# UNI_sensor.net
KiCad netlist of a schematic drawn in Altium Designer
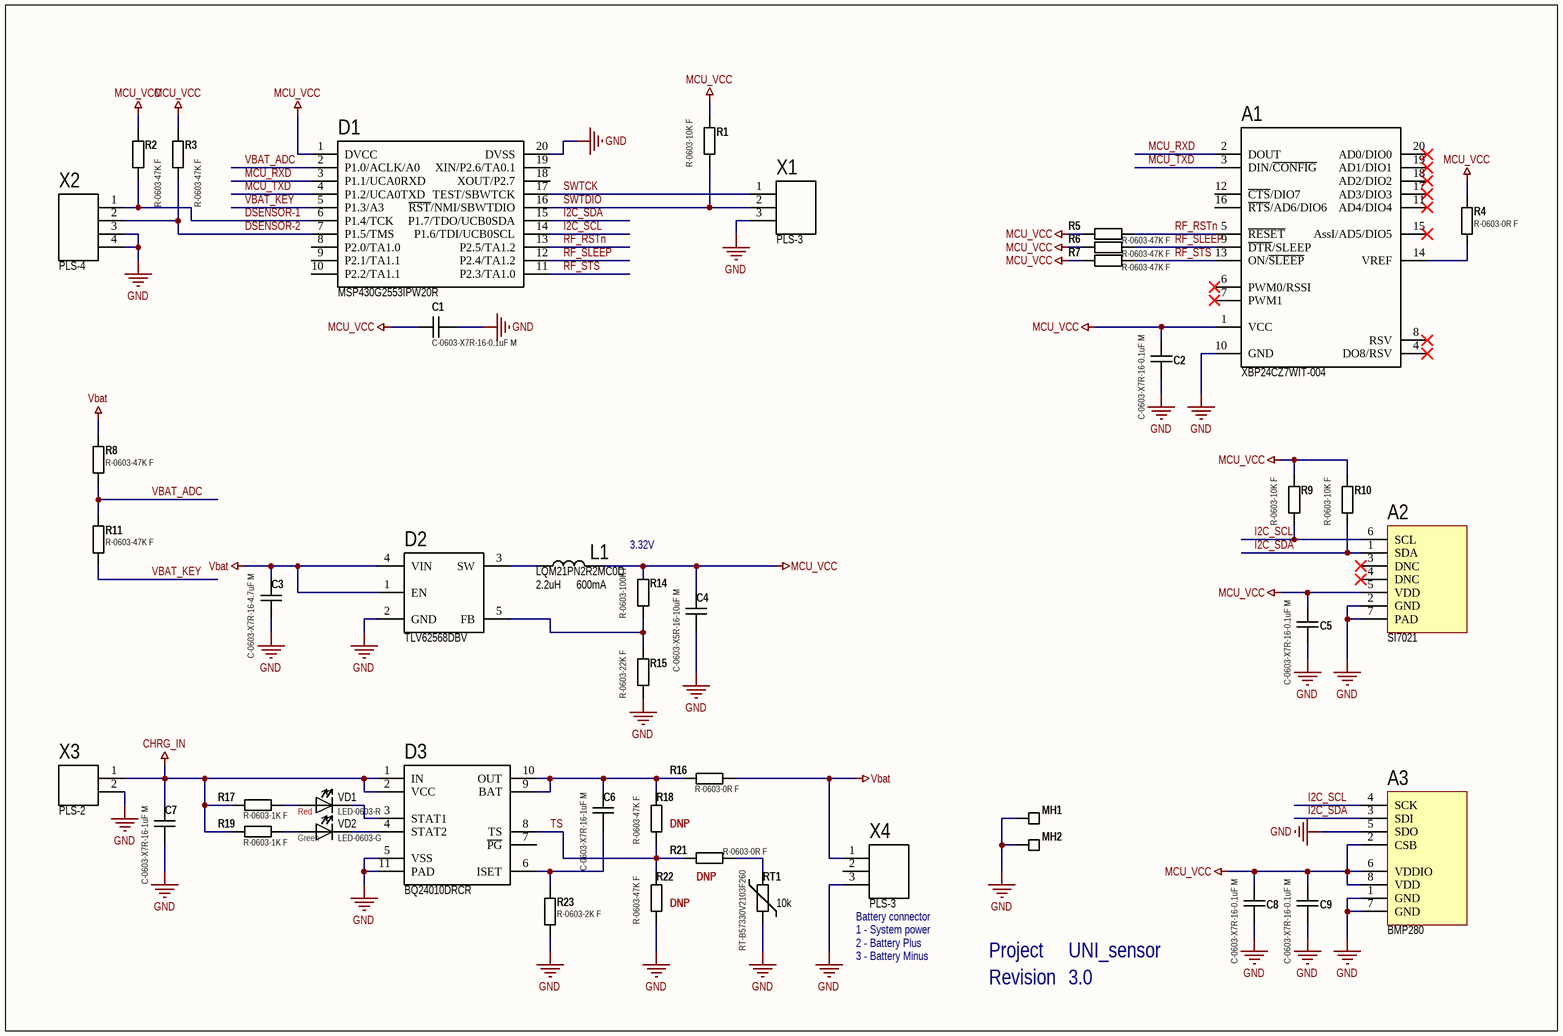
[diagram p0: UNI_sensor.SchDoc]

(export (version "E")
  (design (tool "Eeschema 10.0.6"))
  (components
    (comp (ref "A1")
      (value "XBP24CZ7WIT-004")
      (footprint "XBEE")
      (description "XBee Module")
      (fields (field (name "MANUFACTURER") "Digi"))
      (libsource (lib "Misc") (part "XBP24CZ7WIT"))
    )
    (comp (ref "A2")
      (value "SI7021")
      (footprint "SI7021")
      (description "I2C HUMIDITY AND TEMPERATURE SENSOR")
      (fields (field (name "MANUFACTURER") "Silicon Labs"))
      (libsource (lib "Misc") (part "SI7021"))
    )
    (comp (ref "A3")
      (value "BMP280")
      (footprint "BMP280")
      (description "Digital Pressure Sensor")
      (fields (field (name "MANUFACTURER") "Bosch Sensortec"))
      (libsource (lib "Misc") (part "BMP280"))
    )
    (comp (ref "C1")
      (value "C-0603-X7R-16-0.1uF M")
      (footprint "CAPC160X80X100L35N")
      (description "General capacitor")
      (fields (field (name "TOLERANCE") "20%") (field (name "MANUFACTURER") "Murata"))
      (libsource (lib "Passive") (part "C"))
    )
    (comp (ref "C2")
      (value "C-0603-X7R-16-0.1uF M")
      (footprint "CAPC160X80X100L35N")
      (description "General capacitor")
      (fields (field (name "TOLERANCE") "20%") (field (name "MANUFACTURER") "Murata"))
      (libsource (lib "Passive") (part "C"))
    )
    (comp (ref "C3")
      (value "C-0603-X7R-16-4.7uF M")
      (footprint "CAPC160X80X100L35N")
      (description "General capacitor")
      (fields (field (name "TOLERANCE") "20%") (field (name "MANUFACTURER") "Murata"))
      (libsource (lib "Passive") (part "C"))
    )
    (comp (ref "C4")
      (value "C-0603-X5R-16-10uF M")
      (footprint "CAPC160X80X100L35N")
      (description "General capacitor")
      (fields (field (name "TOLERANCE") "20%") (field (name "MANUFACTURER") "Murata"))
      (libsource (lib "Passive") (part "C"))
    )
    (comp (ref "C5")
      (value "C-0603-X7R-16-0.1uF M")
      (footprint "CAPC160X80X100L35N")
      (description "General capacitor")
      (fields (field (name "TOLERANCE") "20%") (field (name "MANUFACTURER") "Murata"))
      (libsource (lib "Passive") (part "C"))
    )
    (comp (ref "C6")
      (value "C-0603-X7R-16-1uF M")
      (footprint "CAPC160X80X100L35N")
      (description "General capacitor")
      (fields (field (name "TOLERANCE") "20%") (field (name "MANUFACTURER") "Murata"))
      (libsource (lib "Passive") (part "C"))
    )
    (comp (ref "C7")
      (value "C-0603-X7R-16-1uF M")
      (footprint "CAPC160X80X100L35N")
      (description "General capacitor")
      (fields (field (name "TOLERANCE") "20%") (field (name "MANUFACTURER") "Murata"))
      (libsource (lib "Passive") (part "C"))
    )
    (comp (ref "C8")
      (value "C-0603-X7R-16-0.1uF M")
      (footprint "CAPC160X80X100L35N")
      (description "General capacitor")
      (fields (field (name "TOLERANCE") "20%") (field (name "MANUFACTURER") "Murata"))
      (libsource (lib "Passive") (part "C"))
    )
    (comp (ref "C9")
      (value "C-0603-X7R-16-0.1uF M")
      (footprint "CAPC160X80X100L35N")
      (description "General capacitor")
      (fields (field (name "TOLERANCE") "20%") (field (name "MANUFACTURER") "Murata"))
      (libsource (lib "Passive") (part "C"))
    )
    (comp (ref "D1")
      (value "MSP430G2553IPW20R")
      (footprint "TSSOP-20")
      (description "16-bit microcontroller")
      (fields (field (name "MANUFACTURER") "Texas Instruments"))
      (libsource (lib "ICs") (part "MSP430G2553IPW20R"))
    )
    (comp (ref "D2")
      (value "TLV62568DBV")
      (footprint "SOT23-5")
      (description "1-A High Efficiency Synchronous Buck Converterin SOT Package")
      (fields (field (name "MANUFACTURER") "Texas Instruments"))
      (libsource (lib "ICs") (part "TLV62568DBV"))
    )
    (comp (ref "D3")
      (value "BQ24010DRCR")
      (footprint "QFN-11 (3x3)")
      (description "Single-Chip, Li-Ion Charge Management IC for Handheld Applications (bqTINY™)")
      (fields (field (name "MANUFACTURER") "Texas Instruments"))
      (libsource (lib "ICs") (part "BQ24010"))
    )
    (comp (ref "L1")
      (value "LQM21PN2R2MC0D")
      (footprint "L0805_BLM21")
      (description "General inductor")
      (fields
        (field (name "MANUFACTURER") "Murata")
        (field (name "ALTIUM_VALUE") "2.2uH")
        (field (name "TOLERANCE") "20%")
        (field (name "MAXCURRENT") "600mA")
      )
      (libsource (lib "Passive") (part "L"))
    )
    (comp (ref "MH1")
      (value "Testpoint")
      (footprint "REPER_2019:MHole_3.5_6mm")
      (description "Test point")
      (libsource (lib "Main_2019") (part "Test_point"))
    )
    (comp (ref "MH2")
      (value "Testpoint")
      (footprint "REPER_2019:MHole_3.5_6mm")
      (description "Test point")
      (libsource (lib "Main_2019") (part "Test_point"))
    )
    (comp (ref "R1")
      (value "R-0603-10K F")
      (footprint "RESC160X80X55L30N")
      (description "General resistor")
      (fields (field (name "MANUFACTURER") "Yageo") (field (name "TOLERANCE") "1%"))
      (libsource (lib "Passive") (part "R"))
    )
    (comp (ref "R2")
      (value "R-0603-47K F")
      (footprint "RESC160X80X55L30N")
      (description "General resistor")
      (fields (field (name "MANUFACTURER") "Yageo") (field (name "TOLERANCE") "1%"))
      (libsource (lib "Passive") (part "R"))
    )
    (comp (ref "R3")
      (value "R-0603-47K F")
      (footprint "RESC160X80X55L30N")
      (description "General resistor")
      (fields (field (name "MANUFACTURER") "Yageo") (field (name "TOLERANCE") "1%"))
      (libsource (lib "Passive") (part "R"))
    )
    (comp (ref "R4")
      (value "R-0603-0R F")
      (footprint "RESC160X80X55L30N")
      (description "General resistor")
      (fields (field (name "MANUFACTURER") "Yageo"))
      (libsource (lib "Passive") (part "R"))
    )
    (comp (ref "R5")
      (value "R-0603-47K F")
      (footprint "RESC160X80X55L30N")
      (description "General resistor")
      (fields (field (name "MANUFACTURER") "Yageo") (field (name "TOLERANCE") "1%"))
      (libsource (lib "Passive") (part "R"))
    )
    (comp (ref "R6")
      (value "R-0603-47K F")
      (footprint "RESC160X80X55L30N")
      (description "General resistor")
      (fields (field (name "MANUFACTURER") "Yageo") (field (name "TOLERANCE") "1%"))
      (libsource (lib "Passive") (part "R"))
    )
    (comp (ref "R7")
      (value "R-0603-47K F")
      (footprint "RESC160X80X55L30N")
      (description "General resistor")
      (fields (field (name "MANUFACTURER") "Yageo") (field (name "TOLERANCE") "1%"))
      (libsource (lib "Passive") (part "R"))
    )
    (comp (ref "R8")
      (value "R-0603-47K F")
      (footprint "RESC160X80X55L30N")
      (description "General resistor")
      (fields (field (name "MANUFACTURER") "Yageo") (field (name "TOLERANCE") "1%"))
      (libsource (lib "Passive") (part "R"))
    )
    (comp (ref "R9")
      (value "R-0603-10K F")
      (footprint "RESC160X80X55L30N")
      (description "General resistor")
      (fields (field (name "MANUFACTURER") "Yageo") (field (name "TOLERANCE") "1%"))
      (libsource (lib "Passive") (part "R"))
    )
    (comp (ref "R10")
      (value "R-0603-10K F")
      (footprint "RESC160X80X55L30N")
      (description "General resistor")
      (fields (field (name "MANUFACTURER") "Yageo") (field (name "TOLERANCE") "1%"))
      (libsource (lib "Passive") (part "R"))
    )
    (comp (ref "R11")
      (value "R-0603-47K F")
      (footprint "RESC160X80X55L30N")
      (description "General resistor")
      (fields (field (name "MANUFACTURER") "Yageo") (field (name "TOLERANCE") "1%"))
      (libsource (lib "Passive") (part "R"))
    )
    (comp (ref "R14")
      (value "R-0603-100K F")
      (footprint "RESC160X80X55L30N")
      (description "General resistor")
      (fields (field (name "MANUFACTURER") "Yageo") (field (name "TOLERANCE") "1%"))
      (libsource (lib "Passive") (part "R"))
    )
    (comp (ref "R15")
      (value "R-0603-22K F")
      (footprint "RESC160X80X55L30N")
      (description "General resistor")
      (fields (field (name "MANUFACTURER") "Yageo") (field (name "TOLERANCE") "1%"))
      (libsource (lib "Passive") (part "R"))
    )
    (comp (ref "R16")
      (value "R-0603-0R F")
      (footprint "RESC160X80X55L30N")
      (description "General resistor")
      (fields (field (name "MANUFACTURER") "Yageo"))
      (libsource (lib "Passive") (part "R"))
    )
    (comp (ref "R17")
      (value "R-0603-1K F")
      (footprint "RESC160X80X55L30N")
      (description "General resistor")
      (fields (field (name "MANUFACTURER") "Yageo") (field (name "TOLERANCE") "1%"))
      (libsource (lib "Passive") (part "R"))
    )
    (comp (ref "R18")
      (value "R-0603-47K F")
      (footprint "RESC160X80X55L30N")
      (description "General resistor")
      (fields
        (field (name "MANUFACTURER") "Yageo")
        (field (name "TOLERANCE") "1%")
        (field (name "DONOTPLACE") "DNP")
      )
      (libsource (lib "Passive") (part "R"))
    )
    (comp (ref "R19")
      (value "R-0603-1K F")
      (footprint "RESC160X80X55L30N")
      (description "General resistor")
      (fields (field (name "MANUFACTURER") "Yageo") (field (name "TOLERANCE") "1%"))
      (libsource (lib "Passive") (part "R"))
    )
    (comp (ref "R21")
      (value "R-0603-0R F")
      (footprint "RESC160X80X55L30N")
      (description "General resistor")
      (fields (field (name "MANUFACTURER") "Yageo") (field (name "DONOTPLACE") "DNP"))
      (libsource (lib "Passive") (part "R"))
    )
    (comp (ref "R22")
      (value "R-0603-47K F")
      (footprint "RESC160X80X55L30N")
      (description "General resistor")
      (fields
        (field (name "MANUFACTURER") "Yageo")
        (field (name "TOLERANCE") "1%")
        (field (name "DONOTPLACE") "DNP")
      )
      (libsource (lib "Passive") (part "R"))
    )
    (comp (ref "R23")
      (value "R-0603-2K F")
      (footprint "RESC160X80X55L30N")
      (description "General resistor")
      (fields (field (name "MANUFACTURER") "Yageo") (field (name "TOLERANCE") "1%"))
      (libsource (lib "Passive") (part "R"))
    )
    (comp (ref "RT1")
      (value "RT-B57330V2103F260")
      (footprint "RESC160X80X55L30N")
      (description "Thermistor")
      (fields
        (field (name "MANUFACTURER") "Epcos")
        (field (name "PARTNUMBER") "B57330V2103F260")
        (field (name "ALTIUM_VALUE") "10k")
      )
      (libsource (lib "Passive") (part "R_T"))
    )
    (comp (ref "VD1")
      (value "LED-0603-R")
      (footprint "LEDC1608X60N")
      (description "LED")
      (fields (field (name "COLOR") "Red"))
      (libsource (lib "Discrete") (part "LED"))
    )
    (comp (ref "VD2")
      (value "LED-0603-G")
      (footprint "LEDC1608X60N")
      (description "LED")
      (fields (field (name "COLOR") "Green"))
      (libsource (lib "Discrete") (part "LED"))
    )
    (comp (ref "X1")
      (value "PLS-3")
      (footprint "Connector_2019:PLS3")
      (fields (field (name "MANUFACTURER") "KLS"))
      (libsource (lib "Connectors") (part "Conn_3"))
    )
    (comp (ref "X2") (value "PLS-4") (footprint "PLS4") (libsource (lib "Connectors") (part "Conn_4")))
    (comp (ref "X3")
      (value "PLS-2")
      (footprint "Connector_2019:PLS2")
      (fields (field (name "MANUFACTURER") "KLS"))
      (libsource (lib "Connectors") (part "Conn_2"))
    )
    (comp (ref "X4")
      (value "PLS-3")
      (footprint "Connector_2019:PLS3")
      (fields (field (name "MANUFACTURER") "KLS"))
      (libsource (lib "Connectors") (part "Conn_3"))
    )
  )
  (nets
    (net (code "1") (name "/DSENSOR-1") (class "Default")
      (node (ref "D1") (pin "6") (pinfunction "P1.4/TCK_6") (pintype "passive"))
      (node (ref "R2") (pin "1") (pintype "passive"))
      (node (ref "X2") (pin "1") (pinfunction "1_1") (pintype "passive"))
    )
    (net (code "2") (name "/DSENSOR-2") (class "Default")
      (node (ref "D1") (pin "7") (pinfunction "P1.5/TMS_7") (pintype "passive"))
      (node (ref "R3") (pin "1") (pintype "passive"))
      (node (ref "X2") (pin "2") (pinfunction "2_2") (pintype "passive"))
    )
    (net (code "3") (name "/I2C_SCL") (class "Default")
      (node (ref "A2") (pin "6") (pinfunction "SCL_6") (pintype "passive"))
      (node (ref "A3") (pin "4") (pinfunction "SCK_4") (pintype "passive"))
      (node (ref "D1") (pin "14") (pinfunction "P1.6/TDI/UCB0SCL_14") (pintype "passive"))
      (node (ref "R9") (pin "1") (pintype "passive"))
    )
    (net (code "4") (name "/I2C_SDA") (class "Default")
      (node (ref "A2") (pin "1") (pinfunction "SDA_1") (pintype "passive"))
      (node (ref "A3") (pin "3") (pinfunction "SDI_3") (pintype "passive"))
      (node (ref "D1") (pin "15") (pinfunction "P1.7/TDO/UCB0SDA_15") (pintype "passive"))
      (node (ref "R10") (pin "1") (pintype "passive"))
    )
    (net (code "5") (name "/MCU_RXD") (class "Default")
      (node (ref "A1") (pin "2") (pinfunction "DOUT_2") (pintype "passive"))
      (node (ref "D1") (pin "3") (pinfunction "P1.1/UCA0RXD_3") (pintype "passive"))
    )
    (net (code "6") (name "/MCU_TXD") (class "Default")
      (node (ref "A1") (pin "3") (pinfunction "DIN/~{CONFIG}_3") (pintype "passive"))
      (node (ref "D1") (pin "4") (pinfunction "P1.2/UCA0TXD_4") (pintype "passive"))
    )
    (net (code "7") (name "/RF_RSTn") (class "Default")
      (node (ref "A1") (pin "5") (pinfunction "~{RESET}_5") (pintype "passive"))
      (node (ref "D1") (pin "13") (pinfunction "P2.5/TA1.2_13") (pintype "passive"))
      (node (ref "R5") (pin "1") (pintype "passive"))
    )
    (net (code "8") (name "/RF_SLEEP") (class "Default")
      (node (ref "A1") (pin "9") (pinfunction "~{DTR}/SLEEP_9") (pintype "passive"))
      (node (ref "D1") (pin "12") (pinfunction "P2.4/TA1.2_12") (pintype "passive"))
      (node (ref "R6") (pin "1") (pintype "passive"))
    )
    (net (code "9") (name "/RF_STS") (class "Default")
      (node (ref "A1") (pin "13") (pinfunction "ON/~{SLEEP}_13") (pintype "passive"))
      (node (ref "D1") (pin "11") (pinfunction "P2.3/TA1.0_11") (pintype "passive"))
      (node (ref "R7") (pin "1") (pintype "passive"))
    )
    (net (code "10") (name "/SWTCK") (class "Default")
      (node (ref "D1") (pin "17") (pinfunction "TEST/SBWTCK_17") (pintype "passive"))
      (node (ref "X1") (pin "1") (pinfunction "1_1") (pintype "passive"))
    )
    (net (code "11") (name "/SWTDIO") (class "Default")
      (node (ref "D1") (pin "16") (pinfunction "~{RST}/NMI/SBWTDIO_16") (pintype "passive"))
      (node (ref "R1") (pin "1") (pintype "passive"))
      (node (ref "X1") (pin "2") (pinfunction "2_2") (pintype "passive"))
    )
    (net (code "12") (name "/TS") (class "Default")
      (node (ref "D3") (pin "8") (pinfunction "TS_8") (pintype "passive"))
      (node (ref "R18") (pin "1") (pintype "passive"))
      (node (ref "R21") (pin "2") (pintype "passive"))
      (node (ref "R22") (pin "2") (pintype "passive"))
    )
    (net (code "13") (name "/VBAT_ADC") (class "Default")
      (node (ref "D1") (pin "2") (pinfunction "P1.0/ACLK/A0_2") (pintype "passive"))
      (node (ref "R11") (pin "2") (pintype "passive"))
      (node (ref "R8") (pin "1") (pintype "passive"))
    )
    (net (code "14") (name "/VBAT_KEY") (class "Default")
      (node (ref "D1") (pin "5") (pinfunction "P1.3/A3_5") (pintype "passive"))
      (node (ref "R11") (pin "1") (pintype "passive"))
    )
    (net (code "15") (name "CHRG_IN") (class "Default")
      (node (ref "C7") (pin "1") (pintype "passive"))
      (node (ref "D3") (pin "1") (pinfunction "IN_1") (pintype "passive"))
      (node (ref "D3") (pin "2") (pinfunction "VCC_2") (pintype "passive"))
      (node (ref "R17") (pin "1") (pintype "passive"))
      (node (ref "R19") (pin "1") (pintype "passive"))
      (node (ref "X3") (pin "1") (pinfunction "1_1") (pintype "passive"))
    )
    (net (code "16") (name "GND") (class "Default")
      (node (ref "A1") (pin "10") (pinfunction "GND_10") (pintype "passive"))
      (node (ref "A2") (pin "2") (pinfunction "GND_2") (pintype "passive"))
      (node (ref "A2") (pin "7") (pinfunction "PAD_7") (pintype "passive"))
      (node (ref "A3") (pin "1") (pinfunction "GND_1") (pintype "passive"))
      (node (ref "A3") (pin "5") (pinfunction "SDO_5") (pintype "passive"))
      (node (ref "A3") (pin "7") (pinfunction "GND_7") (pintype "passive"))
      (node (ref "C1") (pin "2") (pintype "passive"))
      (node (ref "C2") (pin "2") (pintype "passive"))
      (node (ref "C3") (pin "2") (pintype "passive"))
      (node (ref "C4") (pin "2") (pintype "passive"))
      (node (ref "C5") (pin "2") (pintype "passive"))
      (node (ref "C7") (pin "2") (pintype "passive"))
      (node (ref "C8") (pin "2") (pintype "passive"))
      (node (ref "C9") (pin "2") (pintype "passive"))
      (node (ref "D1") (pin "20") (pinfunction "DVSS_20") (pintype "passive"))
      (node (ref "D2") (pin "2") (pinfunction "GND_2") (pintype "passive"))
      (node (ref "D3") (pin "11") (pinfunction "PAD_11") (pintype "passive"))
      (node (ref "D3") (pin "5") (pinfunction "VSS_5") (pintype "passive"))
      (node (ref "MH1") (pin "1") (pinfunction "1_1") (pintype "passive"))
      (node (ref "MH2") (pin "1") (pinfunction "1_1") (pintype "passive"))
      (node (ref "R15") (pin "1") (pintype "passive"))
      (node (ref "R22") (pin "1") (pintype "passive"))
      (node (ref "R23") (pin "1") (pintype "passive"))
      (node (ref "RT1") (pin "2") (pintype "passive"))
      (node (ref "X1") (pin "3") (pinfunction "3_3") (pintype "passive"))
      (node (ref "X2") (pin "3") (pinfunction "3_3") (pintype "passive"))
      (node (ref "X2") (pin "4") (pinfunction "4_4") (pintype "passive"))
      (node (ref "X3") (pin "2") (pinfunction "2_2") (pintype "passive"))
      (node (ref "X4") (pin "3") (pinfunction "3_3") (pintype "passive"))
    )
    (net (code "17") (name "MCU_VCC") (class "Default")
      (node (ref "A1") (pin "1") (pinfunction "VCC_1") (pintype "passive"))
      (node (ref "A2") (pin "5") (pinfunction "VDD_5") (pintype "passive"))
      (node (ref "A3") (pin "2") (pinfunction "CSB_2") (pintype "passive"))
      (node (ref "A3") (pin "6") (pinfunction "VDDIO_6") (pintype "passive"))
      (node (ref "A3") (pin "8") (pinfunction "VDD_8") (pintype "passive"))
      (node (ref "C1") (pin "1") (pintype "passive"))
      (node (ref "C2") (pin "1") (pintype "passive"))
      (node (ref "C4") (pin "1") (pintype "passive"))
      (node (ref "C5") (pin "1") (pintype "passive"))
      (node (ref "C8") (pin "1") (pintype "passive"))
      (node (ref "C9") (pin "1") (pintype "passive"))
      (node (ref "D1") (pin "1") (pinfunction "DVCC_1") (pintype "passive"))
      (node (ref "L1") (pin "2") (pinfunction "2_2") (pintype "passive"))
      (node (ref "R1") (pin "2") (pintype "passive"))
      (node (ref "R10") (pin "2") (pintype "passive"))
      (node (ref "R14") (pin "2") (pintype "passive"))
      (node (ref "R2") (pin "2") (pintype "passive"))
      (node (ref "R3") (pin "2") (pintype "passive"))
      (node (ref "R4") (pin "1") (pintype "passive"))
      (node (ref "R5") (pin "2") (pintype "passive"))
      (node (ref "R6") (pin "2") (pintype "passive"))
      (node (ref "R7") (pin "2") (pintype "passive"))
      (node (ref "R9") (pin "2") (pintype "passive"))
    )
    (net (code "18") (name "Net-(A1-VREF)") (class "Default")
      (node (ref "A1") (pin "14") (pinfunction "VREF_14") (pintype "passive"))
      (node (ref "R4") (pin "2") (pintype "passive"))
    )
    (net (code "19") (name "Net-(D2-FB)") (class "Default")
      (node (ref "D2") (pin "5") (pinfunction "FB_5") (pintype "passive"))
      (node (ref "R14") (pin "1") (pintype "passive"))
      (node (ref "R15") (pin "2") (pintype "passive"))
    )
    (net (code "20") (name "Net-(D2-SW)") (class "Default")
      (node (ref "D2") (pin "3") (pinfunction "SW_3") (pintype "passive"))
      (node (ref "L1") (pin "1") (pinfunction "1_1") (pintype "passive"))
    )
    (net (code "21") (name "Net-(D3-BAT)") (class "Default")
      (node (ref "C6") (pin "1") (pintype "passive"))
      (node (ref "D3") (pin "10") (pinfunction "OUT_10") (pintype "passive"))
      (node (ref "D3") (pin "9") (pinfunction "BAT_9") (pintype "passive"))
      (node (ref "R16") (pin "2") (pintype "passive"))
      (node (ref "R18") (pin "2") (pintype "passive"))
    )
    (net (code "22") (name "Net-(D3-ISET)") (class "Default")
      (node (ref "C6") (pin "2") (pintype "passive"))
      (node (ref "D3") (pin "6") (pinfunction "ISET_6") (pintype "passive"))
      (node (ref "R23") (pin "2") (pintype "passive"))
    )
    (net (code "23") (name "Net-(D3-STAT1)") (class "Default")
      (node (ref "D3") (pin "3") (pinfunction "STAT1_3") (pintype "passive"))
      (node (ref "VD1") (pin "2") (pinfunction "K_2") (pintype "passive"))
    )
    (net (code "24") (name "Net-(D3-STAT2)") (class "Default")
      (node (ref "D3") (pin "4") (pinfunction "STAT2_4") (pintype "passive"))
      (node (ref "VD2") (pin "2") (pinfunction "K_2") (pintype "passive"))
    )
    (net (code "25") (name "Net-(R21-Pad1)") (class "Default")
      (node (ref "R21") (pin "1") (pintype "passive"))
      (node (ref "RT1") (pin "1") (pintype "passive"))
    )
    (net (code "26") (name "Net-(VD1-A)") (class "Default")
      (node (ref "R17") (pin "2") (pintype "passive"))
      (node (ref "VD1") (pin "1") (pinfunction "A_1") (pintype "passive"))
    )
    (net (code "27") (name "Net-(VD2-A)") (class "Default")
      (node (ref "R19") (pin "2") (pintype "passive"))
      (node (ref "VD2") (pin "1") (pinfunction "A_1") (pintype "passive"))
    )
    (net (code "28") (name "Vbat") (class "Default")
      (node (ref "C3") (pin "1") (pintype "passive"))
      (node (ref "D2") (pin "1") (pinfunction "EN_1") (pintype "passive"))
      (node (ref "D2") (pin "4") (pinfunction "VIN_4") (pintype "passive"))
      (node (ref "R16") (pin "1") (pintype "passive"))
      (node (ref "R8") (pin "2") (pintype "passive"))
      (node (ref "X4") (pin "1") (pinfunction "1_1") (pintype "passive"))
    )
    (net (code "29") (name "unconnected-(A1-AD0{slash}DIO0-Pad20)") (class "Default")
      (node (ref "A1") (pin "20") (pinfunction "AD0/DIO0_20") (pintype "passive+no_connect"))
    )
    (net (code "30") (name "unconnected-(A1-AD1{slash}DIO1-Pad19)") (class "Default")
      (node (ref "A1") (pin "19") (pinfunction "AD1/DIO1_19") (pintype "passive+no_connect"))
    )
    (net (code "31") (name "unconnected-(A1-AD2{slash}DIO2-Pad18)") (class "Default")
      (node (ref "A1") (pin "18") (pinfunction "AD2/DIO2_18") (pintype "passive+no_connect"))
    )
    (net (code "32") (name "unconnected-(A1-AD3{slash}DIO3-Pad17)") (class "Default")
      (node (ref "A1") (pin "17") (pinfunction "AD3/DIO3_17") (pintype "passive+no_connect"))
    )
    (net (code "33") (name "unconnected-(A1-AD4{slash}DIO4-Pad11)") (class "Default")
      (node (ref "A1") (pin "11") (pinfunction "AD4/DIO4_11") (pintype "passive+no_connect"))
    )
    (net (code "34") (name "unconnected-(A1-AssI{slash}AD5{slash}DIO5-Pad15)") (class "Default")
      (node (ref "A1") (pin "15") (pinfunction "AssI/AD5/DIO5_15") (pintype "passive+no_connect"))
    )
    (net (code "35") (name "unconnected-(A1-DO8{slash}RSV-Pad4)") (class "Default")
      (node (ref "A1") (pin "4") (pinfunction "DO8/RSV_4") (pintype "passive+no_connect"))
    )
    (net (code "36") (name "unconnected-(A1-PWM0{slash}RSSI-Pad6)") (class "Default")
      (node (ref "A1") (pin "6") (pinfunction "PWM0/RSSI_6") (pintype "passive+no_connect"))
    )
    (net (code "37") (name "unconnected-(A1-PWM1-Pad7)") (class "Default")
      (node (ref "A1") (pin "7") (pinfunction "PWM1_7") (pintype "passive+no_connect"))
    )
    (net (code "38") (name "unconnected-(A1-RSV-Pad8)") (class "Default")
      (node (ref "A1") (pin "8") (pinfunction "RSV_8") (pintype "passive+no_connect"))
    )
    (net (code "39") (name "unconnected-(A1-~{CTS}{slash}DIO7-Pad12)") (class "Default")
      (node (ref "A1") (pin "12") (pinfunction "~{CTS}/DIO7_12") (pintype "passive"))
    )
    (net (code "40") (name "unconnected-(A1-~{RTS}{slash}AD6{slash}DIO6-Pad16)") (class "Default")
      (node (ref "A1") (pin "16") (pinfunction "~{RTS}/AD6/DIO6_16") (pintype "passive"))
    )
    (net (code "41") (name "unconnected-(A2-DNC-Pad3)") (class "Default")
      (node (ref "A2") (pin "3") (pinfunction "DNC_3") (pintype "passive+no_connect"))
    )
    (net (code "42") (name "unconnected-(A2-DNC-Pad4)") (class "Default")
      (node (ref "A2") (pin "4") (pinfunction "DNC_4") (pintype "passive+no_connect"))
    )
    (net (code "43") (name "unconnected-(D1-P2.0{slash}TA1.0-Pad8)") (class "Default")
      (node (ref "D1") (pin "8") (pinfunction "P2.0/TA1.0_8") (pintype "passive"))
    )
    (net (code "44") (name "unconnected-(D1-P2.1{slash}TA1.1-Pad9)") (class "Default")
      (node (ref "D1") (pin "9") (pinfunction "P2.1/TA1.1_9") (pintype "passive"))
    )
    (net (code "45") (name "unconnected-(D1-P2.2{slash}TA1.1-Pad10)") (class "Default")
      (node (ref "D1") (pin "10") (pinfunction "P2.2/TA1.1_10") (pintype "passive"))
    )
    (net (code "46") (name "unconnected-(D1-XIN{slash}P2.6{slash}TA0.1-Pad19)") (class "Default")
      (node (ref "D1") (pin "19") (pinfunction "XIN/P2.6/TA0.1_19") (pintype "passive"))
    )
    (net (code "47") (name "unconnected-(D1-XOUT{slash}P2.7-Pad18)") (class "Default")
      (node (ref "D1") (pin "18") (pinfunction "XOUT/P2.7_18") (pintype "passive"))
    )
    (net (code "48") (name "unconnected-(D3-~{PG}-Pad7)") (class "Default")
      (node (ref "D3") (pin "7") (pinfunction "~{PG}_7") (pintype "passive"))
    )
    (net (code "49") (name "unconnected-(X4-Pad2)") (class "Default")
      (node (ref "X4") (pin "2") (pinfunction "2_2") (pintype "passive"))
    )
  )
)
